# 01_INPUT_PWR.net
KiCad netlist of a schematic drawn in Altium Designer
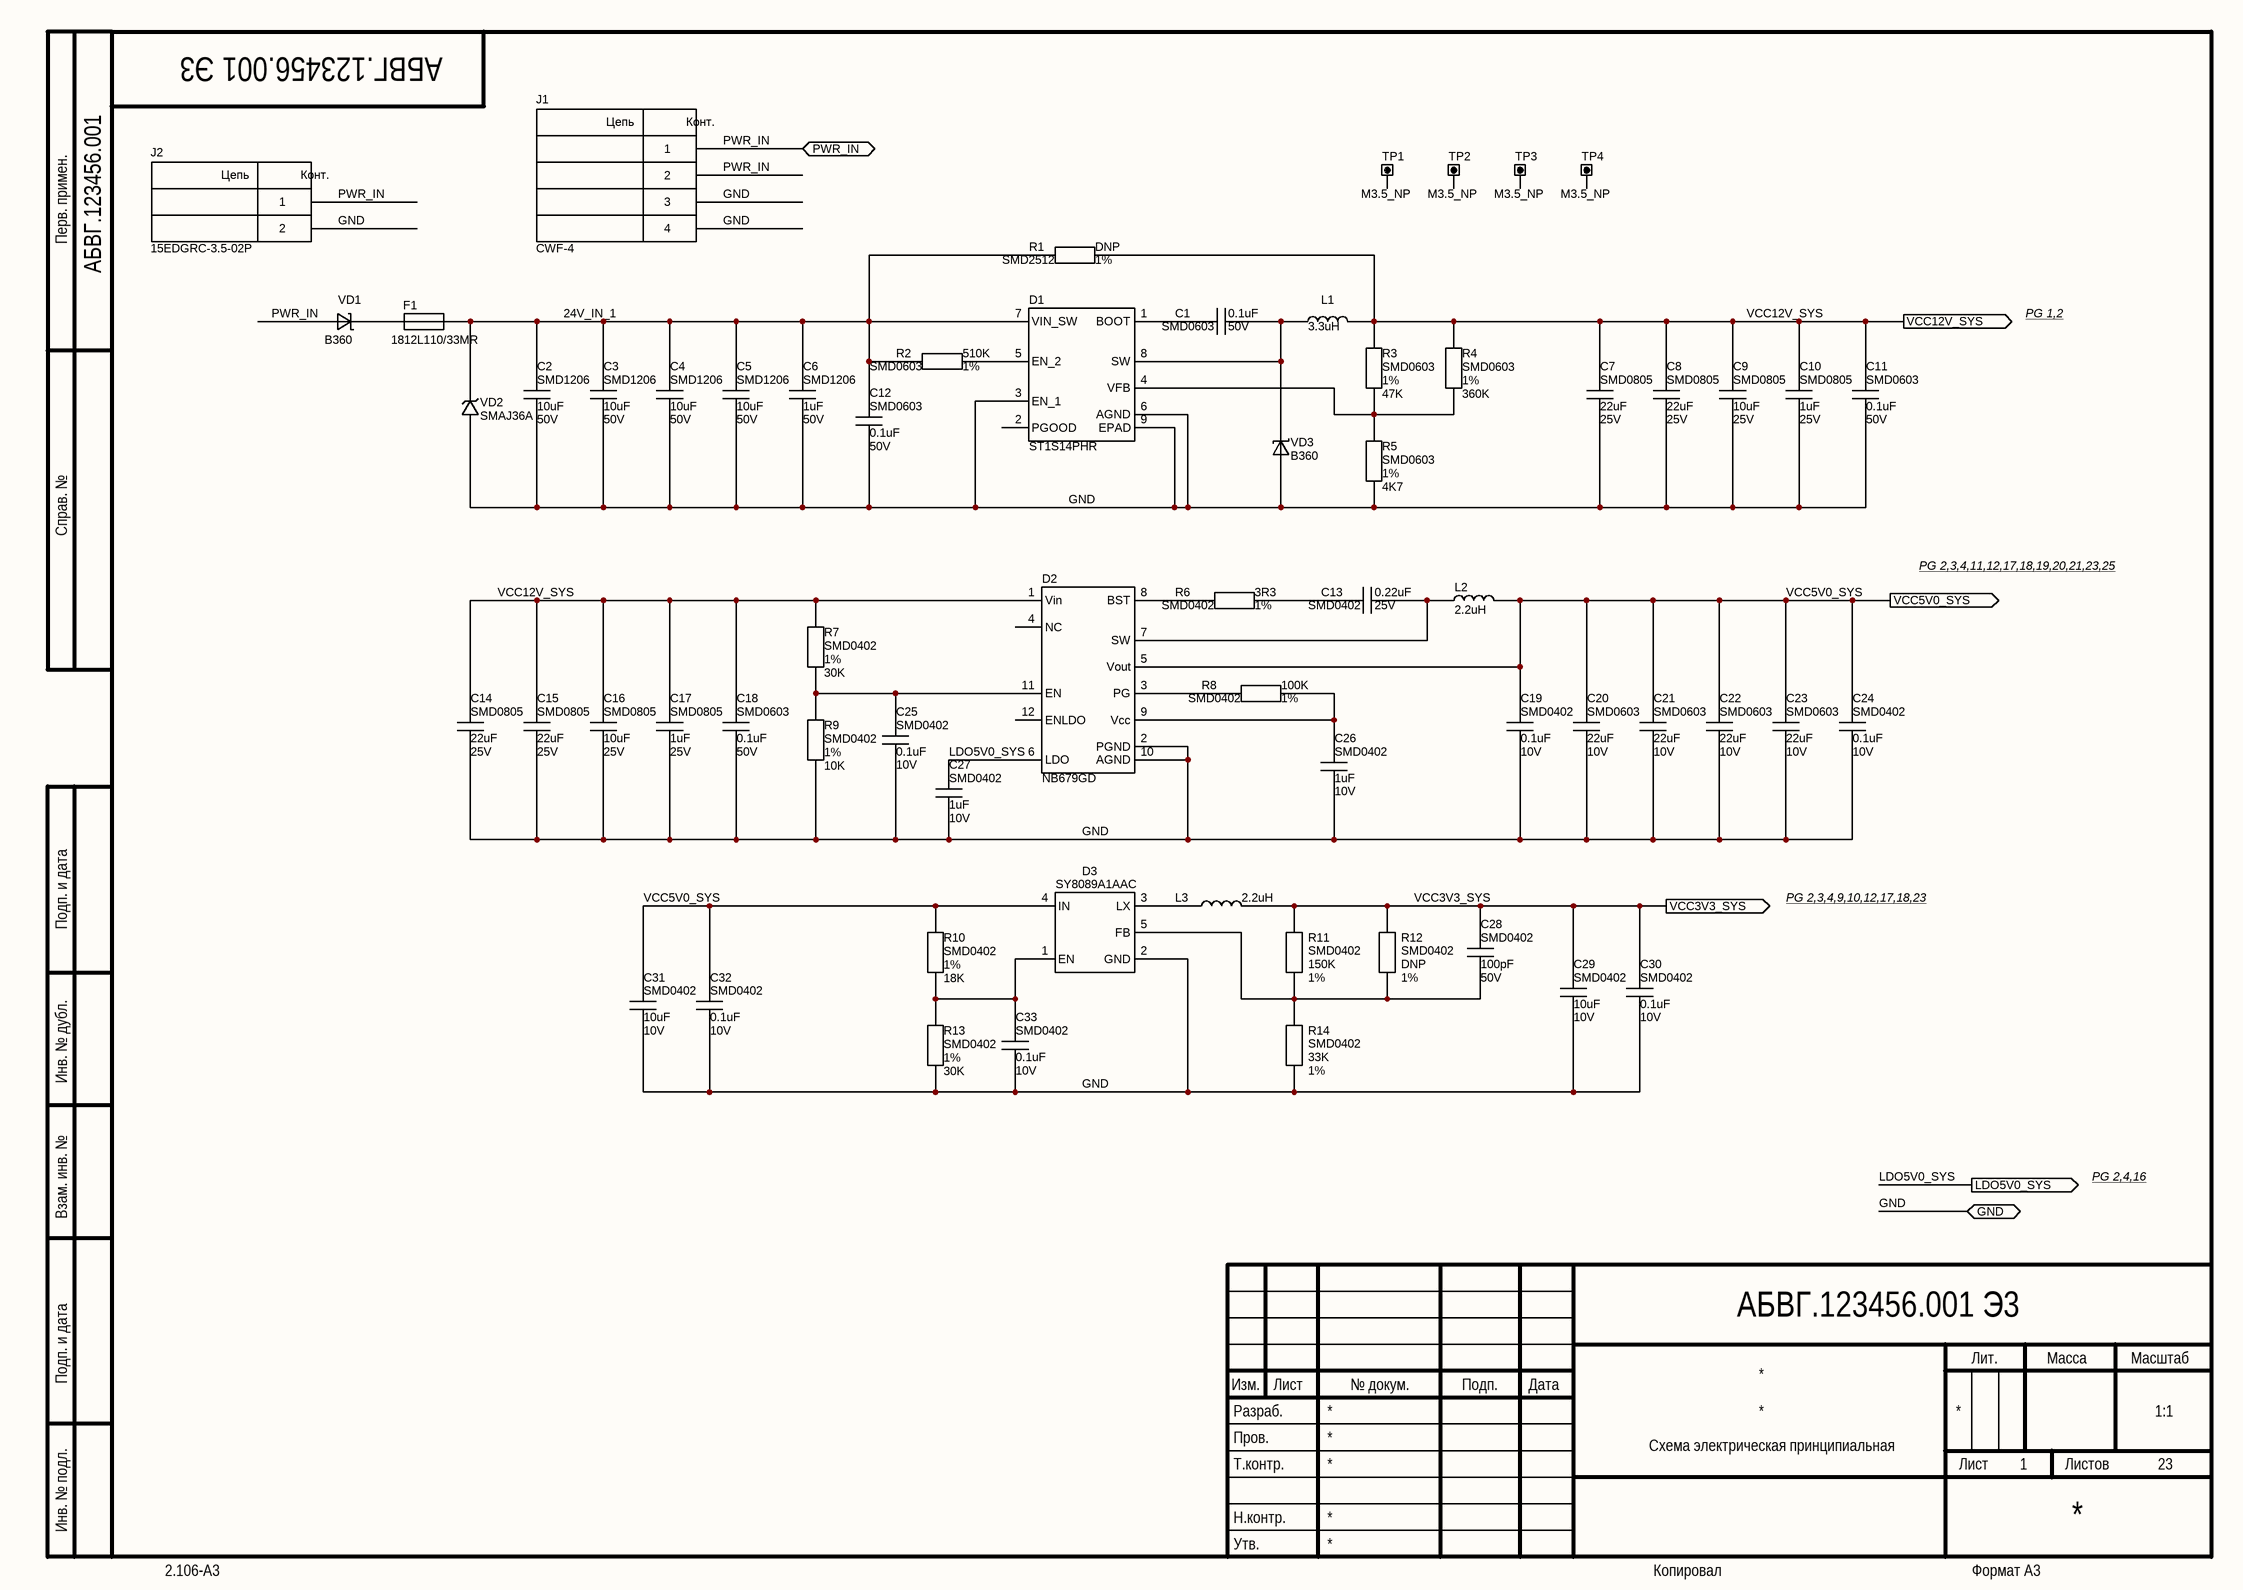
[diagram p0: 01 INPUT_PWR.SchDoc]

(export (version "E")
  (design (tool "Eeschema 10.0.6"))
  (components
    (comp (ref "C1")
      (value "0.1uF")
      (footprint "CAP_SMD_0603")
      (fields
        (field (name "PACKAGE") "SMD0603")
        (field (name "PARTNUMBER") "CC0603KRX7R9BB104")
        (field (name "VOLTAGE") "50V")
      )
      (libsource (lib "Didur_SchLib_1") (part "Ceramic_Cap"))
    )
    (comp (ref "C2")
      (value "10uF")
      (footprint "CAP_SMD_1206")
      (fields
        (field (name "PACKAGE") "SMD1206")
        (field (name "PARTNUMBER") "CL31B106KBHNNNE")
        (field (name "VOLTAGE") "50V")
      )
      (libsource (lib "Didur_SchLib_1") (part "Ceramic_Cap"))
    )
    (comp (ref "C3")
      (value "10uF")
      (footprint "CAP_SMD_1206")
      (fields
        (field (name "PACKAGE") "SMD1206")
        (field (name "PARTNUMBER") "CL31B106KBHNNNE")
        (field (name "VOLTAGE") "50V")
      )
      (libsource (lib "Didur_SchLib_1") (part "Ceramic_Cap"))
    )
    (comp (ref "C4")
      (value "10uF")
      (footprint "CAP_SMD_1206")
      (fields
        (field (name "PACKAGE") "SMD1206")
        (field (name "PARTNUMBER") "CL31B106KBHNNNE")
        (field (name "VOLTAGE") "50V")
      )
      (libsource (lib "Didur_SchLib_1") (part "Ceramic_Cap"))
    )
    (comp (ref "C5")
      (value "10uF")
      (footprint "CAP_SMD_1206")
      (fields
        (field (name "PACKAGE") "SMD1206")
        (field (name "PARTNUMBER") "CL31B106KBHNNNE")
        (field (name "VOLTAGE") "50V")
      )
      (libsource (lib "Didur_SchLib_1") (part "Ceramic_Cap"))
    )
    (comp (ref "C6")
      (value "1uF")
      (footprint "CAP_SMD_1206")
      (fields
        (field (name "PACKAGE") "SMD1206")
        (field (name "PARTNUMBER") "CC1206MRY5V9BB105")
        (field (name "VOLTAGE") "50V")
      )
      (libsource (lib "Didur_SchLib_1") (part "Ceramic_Cap"))
    )
    (comp (ref "C7")
      (value "22uF")
      (footprint "CAP_SMD_0805")
      (fields
        (field (name "PACKAGE") "SMD0805")
        (field (name "PARTNUMBER") "CC0805MKX5R8BB226")
        (field (name "VOLTAGE") "25V")
      )
      (libsource (lib "Didur_SchLib_1") (part "Ceramic_Cap"))
    )
    (comp (ref "C8")
      (value "22uF")
      (footprint "CAP_SMD_0805")
      (fields
        (field (name "PACKAGE") "SMD0805")
        (field (name "PARTNUMBER") "CC0805MKX5R8BB226")
        (field (name "VOLTAGE") "25V")
      )
      (libsource (lib "Didur_SchLib_1") (part "Ceramic_Cap"))
    )
    (comp (ref "C9")
      (value "10uF")
      (footprint "CAP_SMD_0805")
      (fields
        (field (name "PACKAGE") "SMD0805")
        (field (name "PARTNUMBER") "CL21A106KAYNNNE")
        (field (name "VOLTAGE") "25V")
      )
      (libsource (lib "Didur_SchLib_1") (part "Ceramic_Cap"))
    )
    (comp (ref "C10")
      (value "1uF")
      (footprint "CAP_SMD_0805")
      (fields
        (field (name "PACKAGE") "SMD0805")
        (field (name "PARTNUMBER") "CC0805KKX7R8BB105")
        (field (name "VOLTAGE") "25V")
      )
      (libsource (lib "Didur_SchLib_1") (part "Ceramic_Cap"))
    )
    (comp (ref "C11")
      (value "0.1uF")
      (footprint "CAP_SMD_0603")
      (fields
        (field (name "PACKAGE") "SMD0603")
        (field (name "PARTNUMBER") "CC0603KRX7R9BB104")
        (field (name "VOLTAGE") "50V")
      )
      (libsource (lib "Didur_SchLib_1") (part "Ceramic_Cap"))
    )
    (comp (ref "C12")
      (value "0.1uF")
      (footprint "CAP_SMD_0603")
      (fields
        (field (name "PACKAGE") "SMD0603")
        (field (name "PARTNUMBER") "CC0603KRX7R9BB104")
        (field (name "VOLTAGE") "50V")
      )
      (libsource (lib "Didur_SchLib_1") (part "Ceramic_Cap"))
    )
    (comp (ref "C13")
      (value "0.22uF")
      (footprint "Didur_PcbLib_1:CAP_SMD_0402")
      (fields
        (field (name "PACKAGE") "SMD0402")
        (field (name "PARTNUMBER") "CC0402KRX5R8BB224")
        (field (name "VOLTAGE") "25V")
      )
      (libsource (lib "Didur_SchLib_1") (part "Ceramic_Cap"))
    )
    (comp (ref "C14")
      (value "22uF")
      (footprint "CAP_SMD_0805")
      (fields
        (field (name "PACKAGE") "SMD0805")
        (field (name "PARTNUMBER") "CC0805MKX5R8BB226")
        (field (name "VOLTAGE") "25V")
      )
      (libsource (lib "Didur_SchLib_1") (part "Ceramic_Cap"))
    )
    (comp (ref "C15")
      (value "22uF")
      (footprint "CAP_SMD_0805")
      (fields
        (field (name "PACKAGE") "SMD0805")
        (field (name "PARTNUMBER") "CC0805MKX5R8BB226")
        (field (name "VOLTAGE") "25V")
      )
      (libsource (lib "Didur_SchLib_1") (part "Ceramic_Cap"))
    )
    (comp (ref "C16")
      (value "10uF")
      (footprint "CAP_SMD_0805")
      (fields
        (field (name "PACKAGE") "SMD0805")
        (field (name "PARTNUMBER") "CL21A106KAYNNNE")
        (field (name "VOLTAGE") "25V")
      )
      (libsource (lib "Didur_SchLib_1") (part "Ceramic_Cap"))
    )
    (comp (ref "C17")
      (value "1uF")
      (footprint "CAP_SMD_0805")
      (fields
        (field (name "PACKAGE") "SMD0805")
        (field (name "PARTNUMBER") "CC0805KKX7R8BB105")
        (field (name "VOLTAGE") "25V")
      )
      (libsource (lib "Didur_SchLib_1") (part "Ceramic_Cap"))
    )
    (comp (ref "C18")
      (value "0.1uF")
      (footprint "CAP_SMD_0603")
      (fields
        (field (name "PACKAGE") "SMD0603")
        (field (name "PARTNUMBER") "CC0603KRX7R9BB104")
        (field (name "VOLTAGE") "50V")
      )
      (libsource (lib "Didur_SchLib_1") (part "Ceramic_Cap"))
    )
    (comp (ref "C19")
      (value "0.1uF")
      (footprint "Didur_PcbLib_1:CAP_SMD_0402")
      (fields
        (field (name "PACKAGE") "SMD0402")
        (field (name "PARTNUMBER") "CC0402KRX5R6BB104")
        (field (name "VOLTAGE") "10V")
      )
      (libsource (lib "Didur_SchLib_1") (part "Ceramic_Cap"))
    )
    (comp (ref "C20")
      (value "22uF")
      (footprint "CAP_SMD_0603")
      (fields
        (field (name "PACKAGE") "SMD0603")
        (field (name "PARTNUMBER") "CL10A226MP8NUNE")
        (field (name "VOLTAGE") "10V")
      )
      (libsource (lib "Didur_SchLib_1") (part "Ceramic_Cap"))
    )
    (comp (ref "C21")
      (value "22uF")
      (footprint "CAP_SMD_0603")
      (fields
        (field (name "PACKAGE") "SMD0603")
        (field (name "PARTNUMBER") "CL10A226MP8NUNE")
        (field (name "VOLTAGE") "10V")
      )
      (libsource (lib "Didur_SchLib_1") (part "Ceramic_Cap"))
    )
    (comp (ref "C22")
      (value "22uF")
      (footprint "CAP_SMD_0603")
      (fields
        (field (name "PACKAGE") "SMD0603")
        (field (name "PARTNUMBER") "CL10A226MP8NUNE")
        (field (name "VOLTAGE") "10V")
      )
      (libsource (lib "Didur_SchLib_1") (part "Ceramic_Cap"))
    )
    (comp (ref "C23")
      (value "22uF")
      (footprint "CAP_SMD_0603")
      (fields
        (field (name "PACKAGE") "SMD0603")
        (field (name "PARTNUMBER") "CL10A226MP8NUNE")
        (field (name "VOLTAGE") "10V")
      )
      (libsource (lib "Didur_SchLib_1") (part "Ceramic_Cap"))
    )
    (comp (ref "C24")
      (value "0.1uF")
      (footprint "Didur_PcbLib_1:CAP_SMD_0402")
      (fields
        (field (name "PACKAGE") "SMD0402")
        (field (name "PARTNUMBER") "CC0402KRX5R6BB104")
        (field (name "VOLTAGE") "10V")
      )
      (libsource (lib "Didur_SchLib_1") (part "Ceramic_Cap"))
    )
    (comp (ref "C25")
      (value "0.1uF")
      (footprint "Didur_PcbLib_1:CAP_SMD_0402")
      (fields
        (field (name "PACKAGE") "SMD0402")
        (field (name "PARTNUMBER") "CC0402KRX5R6BB104")
        (field (name "VOLTAGE") "10V")
      )
      (libsource (lib "Didur_SchLib_1") (part "Ceramic_Cap"))
    )
    (comp (ref "C26")
      (value "1uF")
      (footprint "Didur_PcbLib_1:CAP_SMD_0402")
      (fields
        (field (name "PACKAGE") "SMD0402")
        (field (name "PARTNUMBER") "CC0402KRX5R6BB105")
        (field (name "VOLTAGE") "10V")
      )
      (libsource (lib "Didur_SchLib_1") (part "Ceramic_Cap"))
    )
    (comp (ref "C27")
      (value "1uF")
      (footprint "Didur_PcbLib_1:CAP_SMD_0402")
      (fields
        (field (name "PACKAGE") "SMD0402")
        (field (name "PARTNUMBER") "CC0402KRX5R6BB105")
        (field (name "VOLTAGE") "10V")
      )
      (libsource (lib "Didur_SchLib_1") (part "Ceramic_Cap"))
    )
    (comp (ref "C28")
      (value "100pF")
      (footprint "Didur_PcbLib_1:CAP_SMD_0402")
      (fields
        (field (name "PACKAGE") "SMD0402")
        (field (name "PARTNUMBER") "CC0402KRNPO9BN101")
        (field (name "VOLTAGE") "50V")
      )
      (libsource (lib "Didur_SchLib_1") (part "Ceramic_Cap"))
    )
    (comp (ref "C29")
      (value "10uF")
      (footprint "Didur_PcbLib_1:CAP_SMD_0402")
      (fields
        (field (name "PACKAGE") "SMD0402")
        (field (name "PARTNUMBER") "CC0402MRX5R6BB106")
        (field (name "VOLTAGE") "10V")
      )
      (libsource (lib "Didur_SchLib_1") (part "Ceramic_Cap"))
    )
    (comp (ref "C30")
      (value "0.1uF")
      (footprint "Didur_PcbLib_1:CAP_SMD_0402")
      (fields
        (field (name "PACKAGE") "SMD0402")
        (field (name "PARTNUMBER") "CC0402KRX5R6BB104")
        (field (name "VOLTAGE") "10V")
      )
      (libsource (lib "Didur_SchLib_1") (part "Ceramic_Cap"))
    )
    (comp (ref "C31")
      (value "10uF")
      (footprint "Didur_PcbLib_1:CAP_SMD_0402")
      (fields
        (field (name "PACKAGE") "SMD0402")
        (field (name "PARTNUMBER") "CC0402MRX5R6BB106")
        (field (name "VOLTAGE") "10V")
      )
      (libsource (lib "Didur_SchLib_1") (part "Ceramic_Cap"))
    )
    (comp (ref "C32")
      (value "0.1uF")
      (footprint "Didur_PcbLib_1:CAP_SMD_0402")
      (fields
        (field (name "PACKAGE") "SMD0402")
        (field (name "PARTNUMBER") "CC0402KRX5R6BB104")
        (field (name "VOLTAGE") "10V")
      )
      (libsource (lib "Didur_SchLib_1") (part "Ceramic_Cap"))
    )
    (comp (ref "C33")
      (value "0.1uF")
      (footprint "Didur_PcbLib_1:CAP_SMD_0402")
      (fields
        (field (name "PACKAGE") "SMD0402")
        (field (name "PARTNUMBER") "CC0402KRX5R6BB104")
        (field (name "VOLTAGE") "10V")
      )
      (libsource (lib "Didur_SchLib_1") (part "Ceramic_Cap"))
    )
    (comp (ref "D1")
      (value "ST1S14PHR")
      (footprint "SO8_PWR")
      (libsource (lib "Didur_SchLib_1") (part "ST1S14"))
    )
    (comp (ref "D2")
      (value "NB679GD")
      (footprint "Didur_PcbLib_1:QFN-12_2mmx3mm")
      (libsource (lib "Didur_SchLib_1") (part "NB679GD"))
    )
    (comp (ref "D3")
      (value "SY8089A1AAC")
      (footprint "Didur_PcbLib_1:SOT23-5")
      (libsource (lib "Didur_SchLib_1") (part "SY8088AAC"))
    )
    (comp (ref "F1")
      (value "1812L110/33MR")
      (footprint "Didur_PcbLib_1:FUSE_SMD_1812")
      (fields (field (name "Comment") "Value"))
      (libsource (lib "Didur_SchLib_1") (part "Fuse"))
    )
    (comp (ref "J1")
      (value "CWF-4")
      (footprint "Didur_PcbLib_1:CWF-4")
      (fields (field (name "PARTNUMBER") "DS1069-4MVW6X (CWF-4)"))
      (libsource (lib "Didur_SchLib_1") (part "CON4"))
    )
    (comp (ref "J2")
      (value "15EDGRC-3.5-02P")
      (footprint "Didur_PcbLib_1:15EDGRC-3.5-02P")
      (libsource (lib "Didur_SchLib_1") (part "CON2"))
    )
    (comp (ref "L1")
      (value "3.3uH")
      (footprint "Didur_PcbLib_1:IHLP2020")
      (fields (field (name "PARTNUMBER") "IHLP2020CZER3R3M01") (field (name "Comment") "Value"))
      (libsource (lib "Didur_SchLib_1") (part "Inductor_smal"))
    )
    (comp (ref "L2")
      (value "2.2uH")
      (footprint "Didur_PcbLib_1:IHLP2020")
      (fields (field (name "PARTNUMBER") "IHLP2020CZER2R2M01") (field (name "Comment") "Value"))
      (libsource (lib "Didur_SchLib_1") (part "Inductor_smal"))
    )
    (comp (ref "L3")
      (value "2.2uH")
      (footprint "Didur_PcbLib_1:HEI252012A")
      (fields (field (name "PARTNUMBER") "HEI252012A-2R2M-Q8") (field (name "Comment") "Value"))
      (libsource (lib "Didur_SchLib_1") (part "Inductor_smal"))
    )
    (comp (ref "R1")
      (value "DNP")
      (footprint "RES_SMD_2512")
      (fields
        (field (name "PACKAGE") "SMD2512")
        (field (name "PARTNUMBER") "RC2512FK-070RL")
        (field (name "TOLERANCE") "1%")
      )
      (libsource (lib "Didur_SchLib_1") (part "Chip_Res"))
    )
    (comp (ref "R2")
      (value "510K")
      (footprint "RES_SMD_0603")
      (fields
        (field (name "PACKAGE") "SMD0603")
        (field (name "PARTNUMBER") "RC0603FR-07510KL")
        (field (name "TOLERANCE") "1%")
      )
      (libsource (lib "Didur_SchLib_1") (part "Chip_Res"))
    )
    (comp (ref "R3")
      (value "47K")
      (footprint "RES_SMD_0603")
      (fields
        (field (name "PACKAGE") "SMD0603")
        (field (name "PARTNUMBER") "RC0603FR-0747KL")
        (field (name "TOLERANCE") "1%")
      )
      (libsource (lib "") (part "Chip_Res_1"))
    )
    (comp (ref "R4")
      (value "360K")
      (footprint "RES_SMD_0603")
      (fields
        (field (name "PACKAGE") "SMD0603")
        (field (name "PARTNUMBER") "RC0603FR-07360KL")
        (field (name "TOLERANCE") "1%")
      )
      (libsource (lib "") (part "Chip_Res_1"))
    )
    (comp (ref "R5")
      (value "4K7")
      (footprint "RES_SMD_0603")
      (fields
        (field (name "PACKAGE") "SMD0603")
        (field (name "PARTNUMBER") "RC0603FR-074K7L")
        (field (name "TOLERANCE") "1%")
      )
      (libsource (lib "") (part "Chip_Res_1"))
    )
    (comp (ref "R6")
      (value "3R3")
      (footprint "Didur_PcbLib_1:RES_SMD_0402")
      (fields
        (field (name "PACKAGE") "SMD0402")
        (field (name "PARTNUMBER") "RC0402FR-073R3L")
        (field (name "TOLERANCE") "1%")
      )
      (libsource (lib "Didur_SchLib_1") (part "Chip_Res"))
    )
    (comp (ref "R7")
      (value "30K")
      (footprint "Didur_PcbLib_1:RES_SMD_0402")
      (fields
        (field (name "PACKAGE") "SMD0402")
        (field (name "PARTNUMBER") "RC0402FR-0730KL")
        (field (name "TOLERANCE") "1%")
      )
      (libsource (lib "") (part "Chip_Res_1"))
    )
    (comp (ref "R8")
      (value "100K")
      (footprint "Didur_PcbLib_1:RES_SMD_0402")
      (fields
        (field (name "PACKAGE") "SMD0402")
        (field (name "PARTNUMBER") "RC0402FR-07100KL")
        (field (name "TOLERANCE") "1%")
      )
      (libsource (lib "") (part "Chip_Res_2"))
    )
    (comp (ref "R9")
      (value "10K")
      (footprint "Didur_PcbLib_1:RES_SMD_0402")
      (fields
        (field (name "PACKAGE") "SMD0402")
        (field (name "PARTNUMBER") "RC0402FR-0710KL")
        (field (name "TOLERANCE") "1%")
      )
      (libsource (lib "") (part "Chip_Res_1"))
    )
    (comp (ref "R10")
      (value "18K")
      (footprint "Didur_PcbLib_1:RES_SMD_0402")
      (fields
        (field (name "PACKAGE") "SMD0402")
        (field (name "PARTNUMBER") "RC0402FR-0718KL")
        (field (name "TOLERANCE") "1%")
      )
      (libsource (lib "") (part "Chip_Res_1"))
    )
    (comp (ref "R11")
      (value "150K")
      (footprint "Didur_PcbLib_1:RES_SMD_0402")
      (fields
        (field (name "PACKAGE") "SMD0402")
        (field (name "PARTNUMBER") "RC0402FR-07150KL")
        (field (name "TOLERANCE") "1%")
      )
      (libsource (lib "Didur_SchLib_1") (part "Chip_Res"))
    )
    (comp (ref "R12")
      (value "DNP")
      (footprint "Didur_PcbLib_1:RES_SMD_0402")
      (fields
        (field (name "PACKAGE") "SMD0402")
        (field (name "PARTNUMBER") "Do Not Place")
        (field (name "TOLERANCE") "1%")
      )
      (libsource (lib "Didur_SchLib_1") (part "Chip_Res"))
    )
    (comp (ref "R13")
      (value "30K")
      (footprint "Didur_PcbLib_1:RES_SMD_0402")
      (fields
        (field (name "PACKAGE") "SMD0402")
        (field (name "PARTNUMBER") "RC0402FR-0730KL")
        (field (name "TOLERANCE") "1%")
      )
      (libsource (lib "") (part "Chip_Res_1"))
    )
    (comp (ref "R14")
      (value "33K")
      (footprint "Didur_PcbLib_1:RES_SMD_0402")
      (fields
        (field (name "PACKAGE") "SMD0402")
        (field (name "PARTNUMBER") "RC0402FR-0733KL")
        (field (name "TOLERANCE") "1%")
      )
      (libsource (lib "Didur_SchLib_1") (part "Chip_Res"))
    )
    (comp (ref "TP1")
      (value "M3.5_NP")
      (footprint "Didur_PcbLib_1:M3.5_NP")
      (libsource (lib "Didur_SchLib_1") (part "TP"))
    )
    (comp (ref "TP2")
      (value "M3.5_NP")
      (footprint "Didur_PcbLib_1:M3.5_NP")
      (libsource (lib "Didur_SchLib_1") (part "TP"))
    )
    (comp (ref "TP3")
      (value "M3.5_NP")
      (footprint "Didur_PcbLib_1:M3.5_NP")
      (libsource (lib "Didur_SchLib_1") (part "TP"))
    )
    (comp (ref "TP4")
      (value "M3.5_NP")
      (footprint "Didur_PcbLib_1:M3.5_NP")
      (libsource (lib "Didur_SchLib_1") (part "TP"))
    )
    (comp (ref "VD1")
      (value "B360")
      (footprint "Didur_PcbLib_1:SMA")
      (fields (field (name "Comment") "Value"))
      (libsource (lib "Didur_SchLib_1") (part "ShottkyDiode"))
    )
    (comp (ref "VD2")
      (value "SMAJ36A")
      (footprint "Didur_PcbLib_1:SMA")
      (libsource (lib "Didur_SchLib_1") (part "ZenerDiode"))
    )
    (comp (ref "VD3")
      (value "B360")
      (footprint "Didur_PcbLib_1:SMA")
      (fields (field (name "Comment") "Value"))
      (libsource (lib "Didur_SchLib_1") (part "ShottkyDiode"))
    )
  )
  (nets
    (net (code "1") (name "/24V_IN_1") (class "Default")
      (node (ref "C12") (pin "2") (pinfunction "2_2") (pintype "power_in"))
      (node (ref "C2") (pin "2") (pinfunction "2_2") (pintype "power_in"))
      (node (ref "C3") (pin "2") (pinfunction "2_2") (pintype "power_in"))
      (node (ref "C4") (pin "2") (pinfunction "2_2") (pintype "power_in"))
      (node (ref "C5") (pin "2") (pinfunction "2_2") (pintype "power_in"))
      (node (ref "C6") (pin "2") (pinfunction "2_2") (pintype "power_in"))
      (node (ref "D1") (pin "7") (pinfunction "VIN_SW_7") (pintype "passive"))
      (node (ref "F1") (pin "2") (pinfunction "2_2") (pintype "passive"))
      (node (ref "R1") (pin "1") (pinfunction "1_1") (pintype "passive"))
      (node (ref "R2") (pin "1") (pinfunction "1_1") (pintype "passive"))
      (node (ref "VD2") (pin "2") (pinfunction "C_2") (pintype "passive"))
    )
    (net (code "2") (name "/GND") (class "Default")
      (node (ref "C10") (pin "1") (pinfunction "1_1") (pintype "power_in"))
      (node (ref "C11") (pin "1") (pinfunction "1_1") (pintype "power_in"))
      (node (ref "C12") (pin "1") (pinfunction "1_1") (pintype "power_in"))
      (node (ref "C14") (pin "1") (pinfunction "1_1") (pintype "power_in"))
      (node (ref "C15") (pin "1") (pinfunction "1_1") (pintype "power_in"))
      (node (ref "C16") (pin "1") (pinfunction "1_1") (pintype "power_in"))
      (node (ref "C17") (pin "1") (pinfunction "1_1") (pintype "power_in"))
      (node (ref "C18") (pin "1") (pinfunction "1_1") (pintype "power_in"))
      (node (ref "C19") (pin "2") (pinfunction "2_2") (pintype "power_in"))
      (node (ref "C2") (pin "1") (pinfunction "1_1") (pintype "power_in"))
      (node (ref "C20") (pin "1") (pinfunction "1_1") (pintype "power_in"))
      (node (ref "C21") (pin "1") (pinfunction "1_1") (pintype "power_in"))
      (node (ref "C22") (pin "1") (pinfunction "1_1") (pintype "power_in"))
      (node (ref "C23") (pin "1") (pinfunction "1_1") (pintype "power_in"))
      (node (ref "C24") (pin "2") (pinfunction "2_2") (pintype "power_in"))
      (node (ref "C25") (pin "2") (pinfunction "2_2") (pintype "power_in"))
      (node (ref "C26") (pin "2") (pinfunction "2_2") (pintype "power_in"))
      (node (ref "C27") (pin "2") (pinfunction "2_2") (pintype "power_in"))
      (node (ref "C29") (pin "2") (pinfunction "2_2") (pintype "power_in"))
      (node (ref "C3") (pin "1") (pinfunction "1_1") (pintype "power_in"))
      (node (ref "C30") (pin "2") (pinfunction "2_2") (pintype "power_in"))
      (node (ref "C31") (pin "2") (pinfunction "2_2") (pintype "power_in"))
      (node (ref "C32") (pin "2") (pinfunction "2_2") (pintype "power_in"))
      (node (ref "C33") (pin "2") (pinfunction "2_2") (pintype "power_in"))
      (node (ref "C4") (pin "1") (pinfunction "1_1") (pintype "power_in"))
      (node (ref "C5") (pin "1") (pinfunction "1_1") (pintype "power_in"))
      (node (ref "C6") (pin "1") (pinfunction "1_1") (pintype "power_in"))
      (node (ref "C7") (pin "1") (pinfunction "1_1") (pintype "power_in"))
      (node (ref "C8") (pin "1") (pinfunction "1_1") (pintype "power_in"))
      (node (ref "C9") (pin "1") (pinfunction "1_1") (pintype "power_in"))
      (node (ref "D1") (pin "3") (pinfunction "EN_1_3") (pintype "passive"))
      (node (ref "D1") (pin "6") (pinfunction "AGND_6") (pintype "passive"))
      (node (ref "D1") (pin "9") (pinfunction "EPAD_9") (pintype "passive"))
      (node (ref "D2") (pin "10") (pinfunction "AGND_10") (pintype "passive"))
      (node (ref "D2") (pin "2") (pinfunction "PGND_2") (pintype "passive"))
      (node (ref "D3") (pin "2") (pinfunction "GND_2") (pintype "passive"))
      (node (ref "J1") (pin "3") (pinfunction "3_3") (pintype "power_in"))
      (node (ref "J1") (pin "4") (pinfunction "4_4") (pintype "power_in"))
      (node (ref "J2") (pin "2") (pinfunction "2_2") (pintype "passive"))
      (node (ref "R13") (pin "1") (pinfunction "1_1") (pintype "passive"))
      (node (ref "R14") (pin "1") (pinfunction "1_1") (pintype "passive"))
      (node (ref "R5") (pin "1") (pinfunction "1_1") (pintype "passive"))
      (node (ref "R9") (pin "1") (pinfunction "1_1") (pintype "passive"))
      (node (ref "VD2") (pin "1") (pinfunction "A_1") (pintype "passive"))
      (node (ref "VD3") (pin "1") (pinfunction "A_1") (pintype "passive"))
    )
    (net (code "3") (name "/LDO5V0_SYS") (class "Default")
      (node (ref "C27") (pin "1") (pinfunction "1_1") (pintype "power_in"))
      (node (ref "D2") (pin "6") (pinfunction "LDO_6") (pintype "passive"))
    )
    (net (code "4") (name "/PWR_IN") (class "Default")
      (node (ref "J1") (pin "1") (pinfunction "1_1") (pintype "passive"))
      (node (ref "J1") (pin "2") (pinfunction "2_2") (pintype "passive"))
      (node (ref "J2") (pin "1") (pinfunction "1_1") (pintype "passive"))
      (node (ref "VD1") (pin "1") (pinfunction "A_1") (pintype "passive"))
    )
    (net (code "5") (name "/VCC3V3_SYS") (class "Default")
      (node (ref "C28") (pin "1") (pinfunction "1_1") (pintype "power_in"))
      (node (ref "C29") (pin "1") (pinfunction "1_1") (pintype "power_in"))
      (node (ref "C30") (pin "1") (pinfunction "1_1") (pintype "power_in"))
      (node (ref "L3") (pin "1") (pinfunction "1_1") (pintype "passive"))
      (node (ref "R11") (pin "2") (pinfunction "2_2") (pintype "passive"))
      (node (ref "R12") (pin "2") (pinfunction "2_2") (pintype "passive"))
    )
    (net (code "6") (name "/VCC5V0_SYS") (class "Default")
      (node (ref "C19") (pin "1") (pinfunction "1_1") (pintype "power_in"))
      (node (ref "C20") (pin "2") (pinfunction "2_2") (pintype "power_in"))
      (node (ref "C21") (pin "2") (pinfunction "2_2") (pintype "power_in"))
      (node (ref "C22") (pin "2") (pinfunction "2_2") (pintype "power_in"))
      (node (ref "C23") (pin "2") (pinfunction "2_2") (pintype "power_in"))
      (node (ref "C24") (pin "1") (pinfunction "1_1") (pintype "power_in"))
      (node (ref "C31") (pin "1") (pinfunction "1_1") (pintype "power_in"))
      (node (ref "C32") (pin "1") (pinfunction "1_1") (pintype "power_in"))
      (node (ref "D2") (pin "5") (pinfunction "Vout_5") (pintype "passive"))
      (node (ref "D3") (pin "4") (pinfunction "IN_4") (pintype "passive"))
      (node (ref "L2") (pin "1") (pinfunction "1_1") (pintype "passive"))
      (node (ref "R10") (pin "2") (pinfunction "2_2") (pintype "passive"))
    )
    (net (code "7") (name "/VCC12V_SYS") (class "Default")
      (node (ref "C10") (pin "2") (pinfunction "2_2") (pintype "power_in"))
      (node (ref "C11") (pin "2") (pinfunction "2_2") (pintype "power_in"))
      (node (ref "C14") (pin "2") (pinfunction "2_2") (pintype "power_in"))
      (node (ref "C15") (pin "2") (pinfunction "2_2") (pintype "power_in"))
      (node (ref "C16") (pin "2") (pinfunction "2_2") (pintype "power_in"))
      (node (ref "C17") (pin "2") (pinfunction "2_2") (pintype "power_in"))
      (node (ref "C18") (pin "2") (pinfunction "2_2") (pintype "power_in"))
      (node (ref "C7") (pin "2") (pinfunction "2_2") (pintype "power_in"))
      (node (ref "C8") (pin "2") (pinfunction "2_2") (pintype "power_in"))
      (node (ref "C9") (pin "2") (pinfunction "2_2") (pintype "power_in"))
      (node (ref "D2") (pin "1") (pinfunction "Vin_1") (pintype "passive"))
      (node (ref "L1") (pin "1") (pinfunction "1_1") (pintype "passive"))
      (node (ref "R1") (pin "2") (pinfunction "2_2") (pintype "passive"))
      (node (ref "R3") (pin "2") (pinfunction "2_2") (pintype "passive"))
      (node (ref "R4") (pin "2") (pinfunction "2_2") (pintype "passive"))
      (node (ref "R7") (pin "2") (pinfunction "2_2") (pintype "passive"))
    )
    (net (code "8") (name "Net-(C13-Pad2)") (class "Default")
      (node (ref "C13") (pin "2") (pinfunction "2_2") (pintype "power_in"))
      (node (ref "R6") (pin "2") (pinfunction "2_2") (pintype "passive"))
    )
    (net (code "9") (name "Net-(D1-BOOT)") (class "Default")
      (node (ref "C1") (pin "2") (pinfunction "2_2") (pintype "power_in"))
      (node (ref "D1") (pin "1") (pinfunction "BOOT_1") (pintype "passive"))
    )
    (net (code "10") (name "Net-(D1-EN_2)") (class "Default")
      (node (ref "D1") (pin "5") (pinfunction "EN_2_5") (pintype "passive"))
      (node (ref "R2") (pin "2") (pinfunction "2_2") (pintype "passive"))
    )
    (net (code "11") (name "Net-(D1-SW)") (class "Default")
      (node (ref "C1") (pin "1") (pinfunction "1_1") (pintype "power_in"))
      (node (ref "D1") (pin "8") (pinfunction "SW_8") (pintype "passive"))
      (node (ref "L1") (pin "2") (pinfunction "2_2") (pintype "passive"))
      (node (ref "VD3") (pin "2") (pinfunction "C_2") (pintype "passive"))
    )
    (net (code "12") (name "Net-(D1-VFB)") (class "Default")
      (node (ref "D1") (pin "4") (pinfunction "VFB_4") (pintype "passive"))
      (node (ref "R3") (pin "1") (pinfunction "1_1") (pintype "passive"))
      (node (ref "R4") (pin "1") (pinfunction "1_1") (pintype "passive"))
      (node (ref "R5") (pin "2") (pinfunction "2_2") (pintype "passive"))
    )
    (net (code "13") (name "Net-(D2-BST)") (class "Default")
      (node (ref "D2") (pin "8") (pinfunction "BST_8") (pintype "passive"))
      (node (ref "R6") (pin "1") (pinfunction "1_1") (pintype "passive"))
    )
    (net (code "14") (name "Net-(D2-EN)") (class "Default")
      (node (ref "C25") (pin "1") (pinfunction "1_1") (pintype "power_in"))
      (node (ref "D2") (pin "11") (pinfunction "EN_11") (pintype "passive"))
      (node (ref "R7") (pin "1") (pinfunction "1_1") (pintype "passive"))
      (node (ref "R9") (pin "2") (pinfunction "2_2") (pintype "passive"))
    )
    (net (code "15") (name "Net-(D2-PG)") (class "Default")
      (node (ref "D2") (pin "3") (pinfunction "PG_3") (pintype "passive"))
      (node (ref "R8") (pin "2") (pinfunction "2_2") (pintype "passive"))
    )
    (net (code "16") (name "Net-(D2-SW)") (class "Default")
      (node (ref "C13") (pin "1") (pinfunction "1_1") (pintype "power_in"))
      (node (ref "D2") (pin "7") (pinfunction "SW_7") (pintype "passive"))
      (node (ref "L2") (pin "2") (pinfunction "2_2") (pintype "passive"))
    )
    (net (code "17") (name "Net-(D2-Vcc)") (class "Default")
      (node (ref "C26") (pin "1") (pinfunction "1_1") (pintype "power_in"))
      (node (ref "D2") (pin "9") (pinfunction "Vcc_9") (pintype "passive"))
      (node (ref "R8") (pin "1") (pinfunction "1_1") (pintype "passive"))
    )
    (net (code "18") (name "Net-(D3-EN)") (class "Default")
      (node (ref "C33") (pin "1") (pinfunction "1_1") (pintype "power_in"))
      (node (ref "D3") (pin "1") (pinfunction "EN_1") (pintype "passive"))
      (node (ref "R10") (pin "1") (pinfunction "1_1") (pintype "passive"))
      (node (ref "R13") (pin "2") (pinfunction "2_2") (pintype "passive"))
    )
    (net (code "19") (name "Net-(D3-FB)") (class "Default")
      (node (ref "C28") (pin "2") (pinfunction "2_2") (pintype "power_in"))
      (node (ref "D3") (pin "5") (pinfunction "FB_5") (pintype "passive"))
      (node (ref "R11") (pin "1") (pinfunction "1_1") (pintype "passive"))
      (node (ref "R12") (pin "1") (pinfunction "1_1") (pintype "passive"))
      (node (ref "R14") (pin "2") (pinfunction "2_2") (pintype "passive"))
    )
    (net (code "20") (name "Net-(D3-LX)") (class "Default")
      (node (ref "D3") (pin "3") (pinfunction "LX_3") (pintype "passive"))
      (node (ref "L3") (pin "2") (pinfunction "2_2") (pintype "passive"))
    )
    (net (code "21") (name "Net-(VD1-C)") (class "Default")
      (node (ref "F1") (pin "1") (pinfunction "1_1") (pintype "passive"))
      (node (ref "VD1") (pin "2") (pinfunction "C_2") (pintype "passive"))
    )
    (net (code "22") (name "unconnected-(D1-PGOOD-Pad2)") (class "Default")
      (node (ref "D1") (pin "2") (pinfunction "PGOOD_2") (pintype "passive"))
    )
    (net (code "23") (name "unconnected-(D2-ENLDO-Pad12)") (class "Default")
      (node (ref "D2") (pin "12") (pinfunction "ENLDO_12") (pintype "passive"))
    )
    (net (code "24") (name "unconnected-(D2-NC-Pad4)") (class "Default")
      (node (ref "D2") (pin "4") (pinfunction "NC_4") (pintype "passive"))
    )
    (net (code "25") (name "unconnected-(TP1-Pad1)") (class "Default")
      (node (ref "TP1") (pin "1") (pinfunction "1_1") (pintype "passive"))
    )
    (net (code "26") (name "unconnected-(TP2-Pad1)") (class "Default")
      (node (ref "TP2") (pin "1") (pinfunction "1_1") (pintype "passive"))
    )
    (net (code "27") (name "unconnected-(TP3-Pad1)") (class "Default")
      (node (ref "TP3") (pin "1") (pinfunction "1_1") (pintype "passive"))
    )
    (net (code "28") (name "unconnected-(TP4-Pad1)") (class "Default")
      (node (ref "TP4") (pin "1") (pinfunction "1_1") (pintype "passive"))
    )
  )
)
